# PSM_footprint_REV_C.net
KiCad netlist of a schematic drawn in Altium Designer
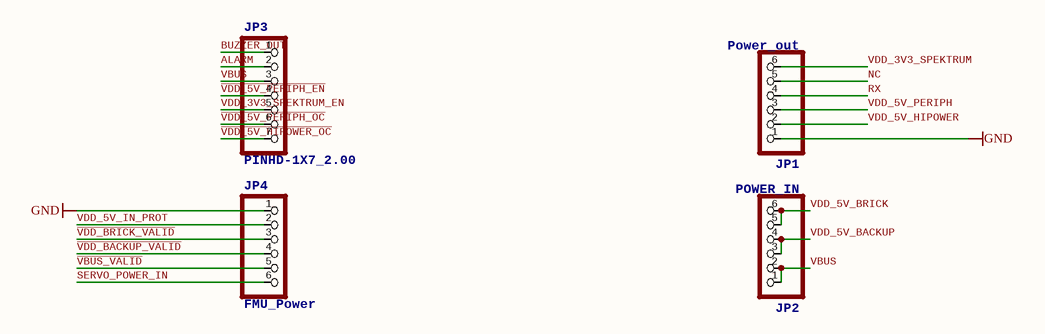
[diagram p0: PSM_footprint_REV_C.SchDoc]

(export (version "E")
  (design (tool "Eeschema 10.0.6"))
  (components
    (comp (ref "JP1")
      (value "Power_out")
      (footprint "1X06M")
      (description "<b>PIN HEADER</b>")
      (libsource (lib "power") (part "PINHD-1X6_2.00"))
    )
    (comp (ref "JP2")
      (value "POWER_IN")
      (footprint "1X06M")
      (description "<b>PIN HEADER</b>")
      (libsource (lib "power") (part "PINHD-1X6_2.00"))
    )
    (comp (ref "JP3")
      (value "PINHD-1X7_2.00")
      (footprint "1X07M")
      (description "<b>PIN HEADER</b>")
      (libsource (lib "power") (part "PINHD-1X7_2.00"))
    )
    (comp (ref "JP4")
      (value "FMU_Power")
      (footprint "1X06M")
      (description "<b>PIN HEADER</b>")
      (libsource (lib "power") (part "PINHD-1X6_2.00"))
    )
  )
  (nets
    (net (code "1") (name "/ALARM") (class "Default")
      (node (ref "JP3") (pin "2") (pinfunction "2_2") (pintype "passive"))
    )
    (net (code "2") (name "/BUZZER_OUT") (class "Default")
      (node (ref "JP3") (pin "1") (pinfunction "1_1") (pintype "passive"))
    )
    (net (code "3") (name "/NC") (class "Default")
      (node (ref "JP1") (pin "5") (pinfunction "5_5") (pintype "passive"))
    )
    (net (code "4") (name "/RX") (class "Default")
      (node (ref "JP1") (pin "4") (pinfunction "4_4") (pintype "passive"))
    )
    (net (code "5") (name "/SERVO_POWER_IN") (class "Default")
      (node (ref "JP4") (pin "6") (pinfunction "6_6") (pintype "passive"))
    )
    (net (code "6") (name "/VBUS") (class "Default")
      (node (ref "JP2") (pin "1") (pinfunction "1_1") (pintype "passive"))
      (node (ref "JP2") (pin "2") (pinfunction "2_2") (pintype "passive"))
      (node (ref "JP3") (pin "3") (pinfunction "3_3") (pintype "passive"))
    )
    (net (code "7") (name "/VDD_3V3_SPEKTRUM") (class "Default")
      (node (ref "JP1") (pin "6") (pinfunction "6_6") (pintype "passive"))
    )
    (net (code "8") (name "/VDD_3V3_SPEKTRUM_EN") (class "Default")
      (node (ref "JP3") (pin "5") (pinfunction "5_5") (pintype "passive"))
    )
    (net (code "9") (name "/VDD_5V_BACKUP") (class "Default")
      (node (ref "JP2") (pin "3") (pinfunction "3_3") (pintype "passive"))
      (node (ref "JP2") (pin "4") (pinfunction "4_4") (pintype "passive"))
    )
    (net (code "10") (name "/VDD_5V_BRICK") (class "Default")
      (node (ref "JP2") (pin "5") (pinfunction "5_5") (pintype "passive"))
      (node (ref "JP2") (pin "6") (pinfunction "6_6") (pintype "passive"))
    )
    (net (code "11") (name "/VDD_5V_HIPOWER") (class "Default")
      (node (ref "JP1") (pin "2") (pinfunction "2_2") (pintype "passive"))
    )
    (net (code "12") (name "/VDD_5V_IN_PROT") (class "Default")
      (node (ref "JP4") (pin "2") (pinfunction "2_2") (pintype "passive"))
    )
    (net (code "13") (name "/VDD_5V_PERIPH") (class "Default")
      (node (ref "JP1") (pin "3") (pinfunction "3_3") (pintype "passive"))
    )
    (net (code "14") (name "/~{VBUS_VALID}") (class "Default")
      (node (ref "JP4") (pin "5") (pinfunction "5_5") (pintype "passive"))
    )
    (net (code "15") (name "/~{VDD_5V_HIPOWER_OC}") (class "Default")
      (node (ref "JP3") (pin "7") (pinfunction "7_7") (pintype "passive"))
    )
    (net (code "16") (name "/~{VDD_5V_PERIPH_EN}") (class "Default")
      (node (ref "JP3") (pin "4") (pinfunction "4_4") (pintype "passive"))
    )
    (net (code "17") (name "/~{VDD_5V_PERIPH_OC}") (class "Default")
      (node (ref "JP3") (pin "6") (pinfunction "6_6") (pintype "passive"))
    )
    (net (code "18") (name "/~{VDD_BACKUP_VALID}") (class "Default")
      (node (ref "JP4") (pin "4") (pinfunction "4_4") (pintype "passive"))
    )
    (net (code "19") (name "/~{VDD_BRICK_VALID}") (class "Default")
      (node (ref "JP4") (pin "3") (pinfunction "3_3") (pintype "passive"))
    )
    (net (code "20") (name "GND") (class "Default")
      (node (ref "JP1") (pin "1") (pinfunction "1_1") (pintype "passive"))
      (node (ref "JP4") (pin "1") (pinfunction "1_1") (pintype "passive"))
    )
  )
)
